# AMU-S24-V00-CURRENTShutdownRelay.net
KiCad netlist of a schematic drawn in Altium Designer
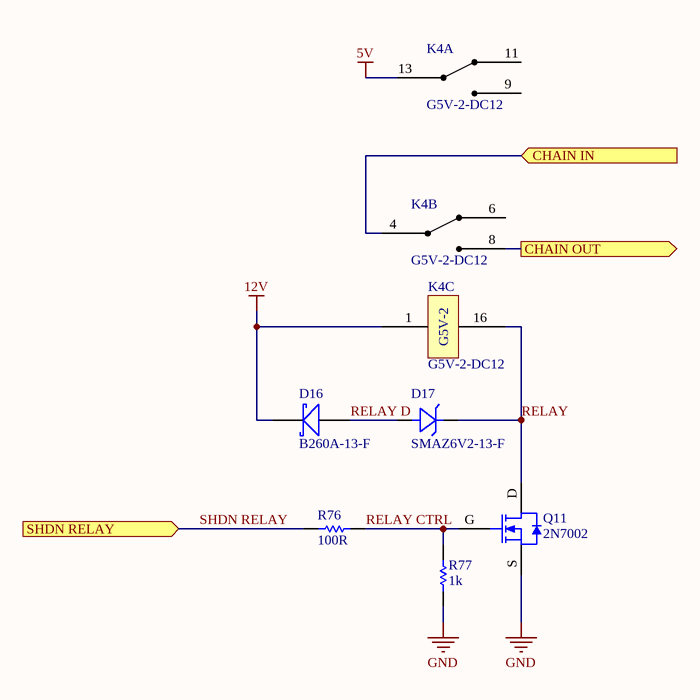
[diagram p0: AMU-S24-V00-CURRENTShutdownRelay.SchDoc]

(export (version "E")
  (design (tool "Eeschema 10.0.6"))
  (components
    (comp (ref "D16")
      (value "B260A-13-F")
      (footprint "SMA")
      (description "Diode, Schottky Barrier Rectifier, 60 V, 2 A, B260A-13-F")
      (libsource (lib "QUTMS_DiodeLibrary") (part "B260A-13-F"))
    )
    (comp (ref "D17")
      (value "SMAZ6V2-13-F")
      (footprint "SMA")
      (description "Zener Diode 6.2V 1W ±5% Surface Mount SMA")
      (fields (field (name "MANUFACTURER") "Generic") (field (name "MPN") "5V6 500mW SMA"))
      (libsource (lib "QUTMS_DiodeLibrary") (part "SMAZ6V2-13-F"))
    )
    (comp (ref "K4")
      (value "G5V-2-DC12")
      (footprint "G5V-2")
      (description "General Purpose Relay DPDT (2 Form C) Through Hole, 12V, 2A")
      (libsource (lib "QUTMS_RelayLibrary") (part "G5V-2-DC12"))
    )
    (comp (ref "Q11")
      (value "2N7002")
      (footprint "SOT23-3")
      (libsource (lib "QUTMS_MOSFETLibrary") (part "2N7002"))
    )
    (comp (ref "R76")
      (value "100R")
      (footprint "Res_ThinFilm_0603")
      (description "Resistor, SMD, 100R, 0.1W, 5%, 0603")
      (libsource (lib "StandardResistors") (part "100R 5%, 0603"))
    )
    (comp (ref "R77")
      (value "1k")
      (footprint "Res_ThinFilm_0603")
      (description "Resistor, SMD, 1k, 0.1W, 5%, 0603")
      (libsource (lib "StandardResistors") (part "1k 5% 0603"))
    )
  )
  (nets
    (net (code "1") (name "/CHAIN IN") (class "Default")
      (node (ref "K4") (pin "4") (pinfunction "4_4") (pintype "passive"))
    )
    (net (code "2") (name "/CHAIN OUT") (class "Default")
      (node (ref "K4") (pin "8") (pinfunction "8_8") (pintype "passive"))
    )
    (net (code "3") (name "/RELAY") (class "Default")
      (node (ref "D17") (pin "K") (pinfunction "Cathode_K") (pintype "passive"))
      (node (ref "K4") (pin "16") (pinfunction "16_16") (pintype "passive"))
      (node (ref "Q11") (pin "D") (pinfunction "D_D") (pintype "passive"))
    )
    (net (code "4") (name "/RELAY CTRL") (class "Default")
      (node (ref "Q11") (pin "G") (pinfunction "G_G") (pintype "passive"))
      (node (ref "R76") (pin "2") (pinfunction "2_2") (pintype "passive"))
      (node (ref "R77") (pin "2") (pinfunction "2_2") (pintype "passive"))
    )
    (net (code "5") (name "/RELAY D") (class "Default")
      (node (ref "D16") (pin "A") (pinfunction "A_A") (pintype "passive"))
      (node (ref "D17") (pin "A") (pinfunction "Anode_A") (pintype "passive"))
    )
    (net (code "6") (name "/SHDN RELAY") (class "Default")
      (node (ref "R76") (pin "1") (pinfunction "1_1") (pintype "passive"))
    )
    (net (code "7") (name "5V") (class "Default")
      (node (ref "K4") (pin "13") (pinfunction "13_13") (pintype "passive"))
    )
    (net (code "8") (name "12V") (class "Default")
      (node (ref "D16") (pin "K") (pinfunction "K_K") (pintype "passive"))
      (node (ref "K4") (pin "1") (pinfunction "1_1") (pintype "passive"))
    )
    (net (code "9") (name "GND") (class "Default")
      (node (ref "Q11") (pin "S") (pinfunction "S_S") (pintype "passive"))
      (node (ref "R77") (pin "1") (pinfunction "1_1") (pintype "passive"))
    )
    (net (code "10") (name "unconnected-(K4-Pad6)") (class "Default")
      (node (ref "K4") (pin "6") (pinfunction "6_6") (pintype "passive"))
    )
    (net (code "11") (name "unconnected-(K4-Pad9)") (class "Default")
      (node (ref "K4") (pin "9") (pinfunction "9_9") (pintype "passive"))
    )
    (net (code "12") (name "unconnected-(K4-Pad11)") (class "Default")
      (node (ref "K4") (pin "11") (pinfunction "11_11") (pintype "passive"))
    )
  )
)
